# Large_Digit_Driver.net
KiCad netlist of a schematic drawn in EAGLE
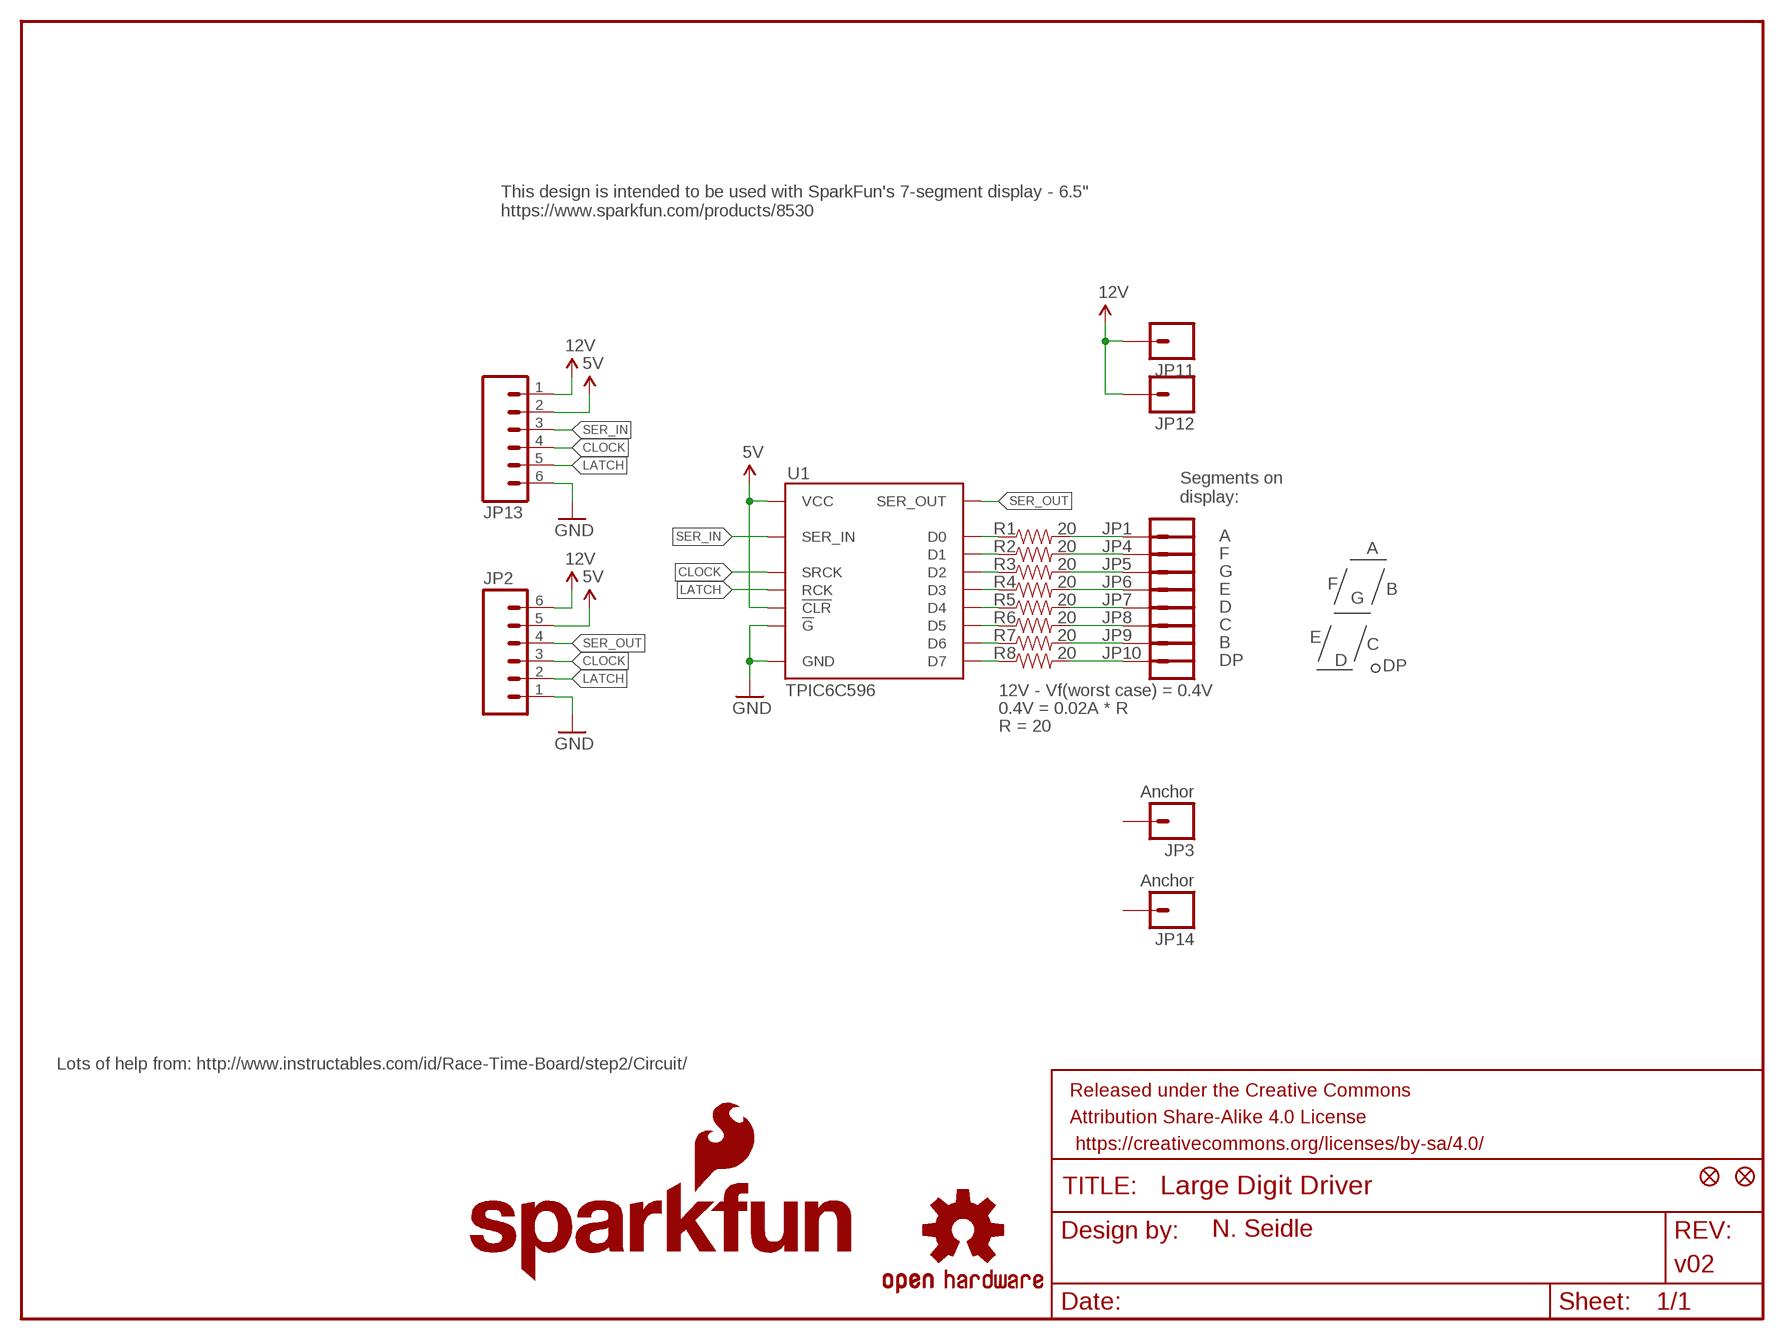
[diagram p0: schematic, sheet 1]

(export (version "E")
  (design (tool "Eeschema 10.0.6"))
  (components
    (comp (ref "FID1")
      (value "FIDUCIAL1X2")
      (footprint "eagle-import:FIDUCIAL-1X2")
      (libsource (lib "eagle-import") (part "FIDUCIAL1X2"))
    )
    (comp (ref "FID2")
      (value "FIDUCIAL1X2")
      (footprint "eagle-import:FIDUCIAL-1X2")
      (libsource (lib "eagle-import") (part "FIDUCIAL1X2"))
    )
    (comp (ref "FRAME1")
      (value "FRAME-LETTER")
      (footprint "eagle-import:CREATIVE_COMMONS")
      (fields (field (name "DESIGNER") "N. Seidle") (field (name "VERSION") "v02"))
      (libsource (lib "eagle-import") (part "FRAME-LETTER"))
    )
    (comp (ref "JP1")
      (value "M01PTH_LONGPAD")
      (footprint "eagle-import:1X01_LONGPAD")
      (libsource (lib "eagle-import") (part "M01PTH_LONGPAD"))
    )
    (comp (ref "JP2")
      (value "M06SMD")
      (footprint "eagle-import:1X06-SMD")
      (libsource (lib "eagle-import") (part "M06SMD"))
    )
    (comp (ref "JP3")
      (value "Anchor")
      (footprint "eagle-import:1X01_LONGPAD")
      (libsource (lib "eagle-import") (part "M01PTH_LONGPAD"))
    )
    (comp (ref "JP4")
      (value "M01PTH_LONGPAD")
      (footprint "eagle-import:1X01_LONGPAD")
      (libsource (lib "eagle-import") (part "M01PTH_LONGPAD"))
    )
    (comp (ref "JP5")
      (value "M01PTH_LONGPAD")
      (footprint "eagle-import:1X01_LONGPAD")
      (libsource (lib "eagle-import") (part "M01PTH_LONGPAD"))
    )
    (comp (ref "JP6")
      (value "M01PTH_LONGPAD")
      (footprint "eagle-import:1X01_LONGPAD")
      (libsource (lib "eagle-import") (part "M01PTH_LONGPAD"))
    )
    (comp (ref "JP7")
      (value "M01PTH_LONGPAD")
      (footprint "eagle-import:1X01_LONGPAD")
      (libsource (lib "eagle-import") (part "M01PTH_LONGPAD"))
    )
    (comp (ref "JP8")
      (value "M01PTH_LONGPAD")
      (footprint "eagle-import:1X01_LONGPAD")
      (libsource (lib "eagle-import") (part "M01PTH_LONGPAD"))
    )
    (comp (ref "JP9")
      (value "M01PTH_LONGPAD")
      (footprint "eagle-import:1X01_LONGPAD")
      (libsource (lib "eagle-import") (part "M01PTH_LONGPAD"))
    )
    (comp (ref "JP10")
      (value "M01PTH_LONGPAD")
      (footprint "eagle-import:1X01_LONGPAD")
      (libsource (lib "eagle-import") (part "M01PTH_LONGPAD"))
    )
    (comp (ref "JP11")
      (value "M01PTH_LONGPAD")
      (footprint "eagle-import:1X01_LONGPAD")
      (libsource (lib "eagle-import") (part "M01PTH_LONGPAD"))
    )
    (comp (ref "JP12")
      (value "M01PTH_LONGPAD")
      (footprint "eagle-import:1X01_LONGPAD")
      (libsource (lib "eagle-import") (part "M01PTH_LONGPAD"))
    )
    (comp (ref "JP13")
      (value "M06SMD")
      (footprint "eagle-import:1X06-SMD")
      (libsource (lib "eagle-import") (part "M06SMD"))
    )
    (comp (ref "JP14")
      (value "Anchor")
      (footprint "eagle-import:1X01_LONGPAD")
      (libsource (lib "eagle-import") (part "M01PTH_LONGPAD"))
    )
    (comp (ref "LOGO1")
      (value "SFE_LOGO_NAME_FLAME.1_INCH")
      (footprint "eagle-import:SFE_LOGO_NAME_FLAME_.1")
      (libsource (lib "eagle-import") (part "SFE_LOGO_NAME_FLAME.1_INCH"))
    )
    (comp (ref "LOGO2")
      (value "OSHW-LOGOS")
      (footprint "eagle-import:OSHW-LOGO-S")
      (libsource (lib "eagle-import") (part "OSHW-LOGOS"))
    )
    (comp (ref "R1")
      (value "20")
      (footprint "eagle-import:0603-RES")
      (libsource (lib "eagle-import") (part "20OHM1/10W1%(0603)SMD"))
    )
    (comp (ref "R2")
      (value "20")
      (footprint "eagle-import:0603-RES")
      (libsource (lib "eagle-import") (part "20OHM1/10W1%(0603)SMD"))
    )
    (comp (ref "R3")
      (value "20")
      (footprint "eagle-import:0603-RES")
      (libsource (lib "eagle-import") (part "20OHM1/10W1%(0603)SMD"))
    )
    (comp (ref "R4")
      (value "20")
      (footprint "eagle-import:0603-RES")
      (libsource (lib "eagle-import") (part "20OHM1/10W1%(0603)SMD"))
    )
    (comp (ref "R5")
      (value "20")
      (footprint "eagle-import:0603-RES")
      (libsource (lib "eagle-import") (part "20OHM1/10W1%(0603)SMD"))
    )
    (comp (ref "R6")
      (value "20")
      (footprint "eagle-import:0603-RES")
      (libsource (lib "eagle-import") (part "20OHM1/10W1%(0603)SMD"))
    )
    (comp (ref "R7")
      (value "20")
      (footprint "eagle-import:0603-RES")
      (libsource (lib "eagle-import") (part "20OHM1/10W1%(0603)SMD"))
    )
    (comp (ref "R8")
      (value "20")
      (footprint "eagle-import:0603-RES")
      (libsource (lib "eagle-import") (part "20OHM1/10W1%(0603)SMD"))
    )
    (comp (ref "U1")
      (value "TPIC6C596")
      (footprint "eagle-import:SO016")
      (libsource (lib "eagle-import") (part "TPIC6C596SOIC"))
    )
  )
  (nets
    (net (code "1") (name "5V") (class "Default")
      (node (ref "JP13") (pin "2") (pinfunction "2_2") (pintype "passive"))
      (node (ref "JP2") (pin "5") (pinfunction "5_5") (pintype "passive"))
      (node (ref "U1") (pin "1") (pinfunction "VCC_1") (pintype "power_in"))
      (node (ref "U1") (pin "7") (pinfunction "~{CLR}_7") (pintype "input"))
    )
    (net (code "2") (name "12V") (class "Default")
      (node (ref "JP11") (pin "1") (pinfunction "1_1") (pintype "passive"))
      (node (ref "JP12") (pin "1") (pinfunction "1_1") (pintype "passive"))
      (node (ref "JP13") (pin "1") (pinfunction "1_1") (pintype "passive"))
      (node (ref "JP2") (pin "6") (pinfunction "6_6") (pintype "passive"))
    )
    (net (code "3") (name "CLOCK") (class "Default")
      (node (ref "JP13") (pin "4") (pinfunction "4_4") (pintype "passive"))
      (node (ref "JP2") (pin "3") (pinfunction "3_3") (pintype "passive"))
      (node (ref "U1") (pin "15") (pinfunction "SRCK_15") (pintype "input"))
    )
    (net (code "4") (name "GND") (class "Default")
      (node (ref "JP13") (pin "6") (pinfunction "6_6") (pintype "passive"))
      (node (ref "JP2") (pin "1") (pinfunction "1_1") (pintype "passive"))
      (node (ref "U1") (pin "16") (pinfunction "GND_16") (pintype "power_in"))
      (node (ref "U1") (pin "8") (pinfunction "~{G}_8") (pintype "input"))
    )
    (net (code "5") (name "LATCH") (class "Default")
      (node (ref "JP13") (pin "5") (pinfunction "5_5") (pintype "passive"))
      (node (ref "JP2") (pin "2") (pinfunction "2_2") (pintype "passive"))
      (node (ref "U1") (pin "10") (pinfunction "RCK_10") (pintype "input"))
    )
    (net (code "6") (name "Net-(JP1-Pad1)") (class "Default")
      (node (ref "JP1") (pin "1") (pinfunction "1_1") (pintype "passive"))
      (node (ref "R1") (pin "2") (pinfunction "2_2") (pintype "passive"))
    )
    (net (code "7") (name "Net-(JP4-Pad1)") (class "Default")
      (node (ref "JP4") (pin "1") (pinfunction "1_1") (pintype "passive"))
      (node (ref "R2") (pin "2") (pinfunction "2_2") (pintype "passive"))
    )
    (net (code "8") (name "Net-(JP5-Pad1)") (class "Default")
      (node (ref "JP5") (pin "1") (pinfunction "1_1") (pintype "passive"))
      (node (ref "R3") (pin "2") (pinfunction "2_2") (pintype "passive"))
    )
    (net (code "9") (name "Net-(JP6-Pad1)") (class "Default")
      (node (ref "JP6") (pin "1") (pinfunction "1_1") (pintype "passive"))
      (node (ref "R4") (pin "2") (pinfunction "2_2") (pintype "passive"))
    )
    (net (code "10") (name "Net-(JP7-Pad1)") (class "Default")
      (node (ref "JP7") (pin "1") (pinfunction "1_1") (pintype "passive"))
      (node (ref "R5") (pin "2") (pinfunction "2_2") (pintype "passive"))
    )
    (net (code "11") (name "Net-(JP8-Pad1)") (class "Default")
      (node (ref "JP8") (pin "1") (pinfunction "1_1") (pintype "passive"))
      (node (ref "R6") (pin "2") (pinfunction "2_2") (pintype "passive"))
    )
    (net (code "12") (name "Net-(JP9-Pad1)") (class "Default")
      (node (ref "JP9") (pin "1") (pinfunction "1_1") (pintype "passive"))
      (node (ref "R7") (pin "2") (pinfunction "2_2") (pintype "passive"))
    )
    (net (code "13") (name "Net-(JP10-Pad1)") (class "Default")
      (node (ref "JP10") (pin "1") (pinfunction "1_1") (pintype "passive"))
      (node (ref "R8") (pin "2") (pinfunction "2_2") (pintype "passive"))
    )
    (net (code "14") (name "Net-(U1-D0)") (class "Default")
      (node (ref "R1") (pin "1") (pinfunction "1_1") (pintype "passive"))
      (node (ref "U1") (pin "3") (pinfunction "D0_3") (pintype "output"))
    )
    (net (code "15") (name "Net-(U1-D1)") (class "Default")
      (node (ref "R2") (pin "1") (pinfunction "1_1") (pintype "passive"))
      (node (ref "U1") (pin "4") (pinfunction "D1_4") (pintype "output"))
    )
    (net (code "16") (name "Net-(U1-D2)") (class "Default")
      (node (ref "R3") (pin "1") (pinfunction "1_1") (pintype "passive"))
      (node (ref "U1") (pin "5") (pinfunction "D2_5") (pintype "output"))
    )
    (net (code "17") (name "Net-(U1-D3)") (class "Default")
      (node (ref "R4") (pin "1") (pinfunction "1_1") (pintype "passive"))
      (node (ref "U1") (pin "6") (pinfunction "D3_6") (pintype "output"))
    )
    (net (code "18") (name "Net-(U1-D4)") (class "Default")
      (node (ref "R5") (pin "1") (pinfunction "1_1") (pintype "passive"))
      (node (ref "U1") (pin "11") (pinfunction "D4_11") (pintype "output"))
    )
    (net (code "19") (name "Net-(U1-D5)") (class "Default")
      (node (ref "R6") (pin "1") (pinfunction "1_1") (pintype "passive"))
      (node (ref "U1") (pin "12") (pinfunction "D5_12") (pintype "output"))
    )
    (net (code "20") (name "Net-(U1-D6)") (class "Default")
      (node (ref "R7") (pin "1") (pinfunction "1_1") (pintype "passive"))
      (node (ref "U1") (pin "13") (pinfunction "D6_13") (pintype "output"))
    )
    (net (code "21") (name "Net-(U1-D7)") (class "Default")
      (node (ref "R8") (pin "1") (pinfunction "1_1") (pintype "passive"))
      (node (ref "U1") (pin "14") (pinfunction "D7_14") (pintype "output"))
    )
    (net (code "22") (name "SER_IN") (class "Default")
      (node (ref "JP13") (pin "3") (pinfunction "3_3") (pintype "passive"))
      (node (ref "U1") (pin "2") (pinfunction "SER_IN_2") (pintype "input"))
    )
    (net (code "23") (name "SER_OUT") (class "Default")
      (node (ref "JP2") (pin "4") (pinfunction "4_4") (pintype "passive"))
      (node (ref "U1") (pin "9") (pinfunction "SER_OUT_9") (pintype "output"))
    )
    (net (code "24") (name "unconnected-(JP3-Pad1)") (class "Default")
      (node (ref "JP3") (pin "1") (pinfunction "1_1") (pintype "passive"))
    )
    (net (code "25") (name "unconnected-(JP14-Pad1)") (class "Default")
      (node (ref "JP14") (pin "1") (pinfunction "1_1") (pintype "passive"))
    )
  )
)
